# BareBonesArduino-OtherMill-BottomOnly.net
KiCad netlist of a schematic drawn in EAGLE
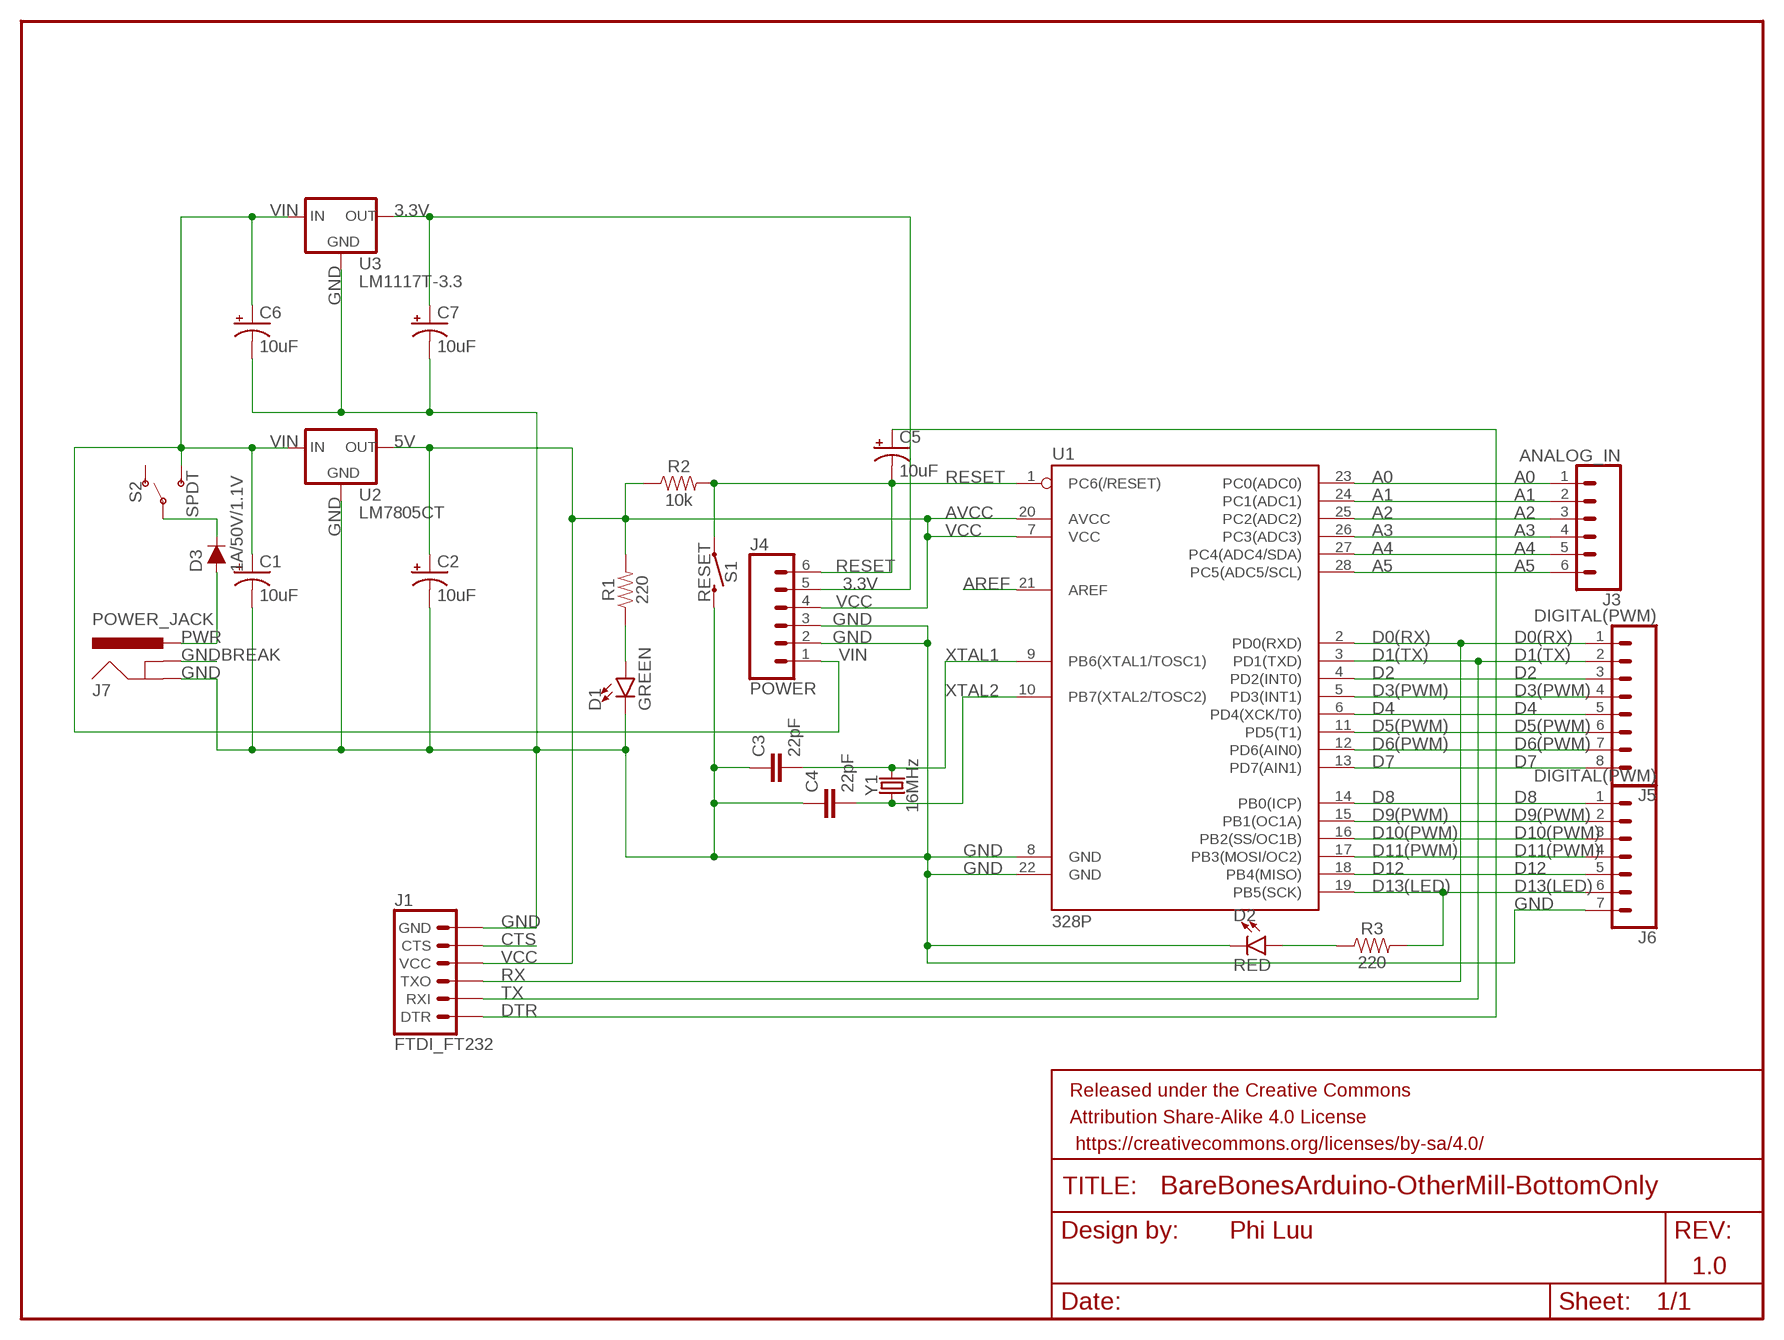
[diagram p0: schematic, sheet 1]

(export (version "E")
  (design (tool "Eeschema 10.0.6"))
  (components
    (comp (ref "C1")
      (value "10uF")
      (footprint "eagle-import:CPOL-RADIAL-2.5MM-5MM")
      (libsource (lib "eagle-import") (part "10UF-POLAR-RADIAL-2.5MM-25V-20%"))
    )
    (comp (ref "C2")
      (value "10uF")
      (footprint "eagle-import:CPOL-RADIAL-2.5MM-5MM")
      (libsource (lib "eagle-import") (part "10UF-POLAR-RADIAL-2.5MM-25V-20%"))
    )
    (comp (ref "C3")
      (value "22pF")
      (footprint "eagle-import:CAP-PTH-2.54")
      (libsource (lib "eagle-import") (part "22PF-PTH-2.54MM-200V-5%"))
    )
    (comp (ref "C4")
      (value "22pF")
      (footprint "eagle-import:CAP-PTH-2.54")
      (libsource (lib "eagle-import") (part "22PF-PTH-2.54MM-200V-5%"))
    )
    (comp (ref "C5")
      (value "10uF")
      (footprint "eagle-import:CPOL-RADIAL-2.5MM-5MM")
      (libsource (lib "eagle-import") (part "10UF-POLAR-RADIAL-2.5MM-25V-20%"))
    )
    (comp (ref "C6")
      (value "10uF")
      (footprint "eagle-import:CPOL-RADIAL-2.5MM-5MM")
      (libsource (lib "eagle-import") (part "10UF-POLAR-RADIAL-2.5MM-25V-20%"))
    )
    (comp (ref "C7")
      (value "10uF")
      (footprint "eagle-import:CPOL-RADIAL-2.5MM-5MM")
      (libsource (lib "eagle-import") (part "10UF-POLAR-RADIAL-2.5MM-25V-20%"))
    )
    (comp (ref "D1")
      (value "GREEN")
      (footprint "eagle-import:LED_5MM")
      (libsource (lib "eagle-import") (part "LED5MM"))
    )
    (comp (ref "D2")
      (value "RED")
      (footprint "eagle-import:LED_5MM")
      (libsource (lib "eagle-import") (part "LED5MM"))
    )
    (comp (ref "D3")
      (value "1A/50V/1.1V")
      (footprint "eagle-import:DIODE-1N4001")
      (libsource (lib "eagle-import") (part "DIODE-PTH"))
    )
    (comp (ref "FRAME1")
      (value "FRAME-LETTER")
      (footprint "eagle-import:CREATIVE_COMMONS")
      (libsource (lib "eagle-import") (part "FRAME-LETTER"))
    )
    (comp (ref "J1")
      (value "FTDI_FT232")
      (footprint "eagle-import:1X06")
      (libsource (lib "eagle-import") (part "6_PIN_SERIAL_TARGET"))
    )
    (comp (ref "J3")
      (value "ANALOG_IN")
      (footprint "eagle-import:1X06")
      (libsource (lib "eagle-import") (part "CONN_06SILK_FEMALE_PTH"))
    )
    (comp (ref "J4")
      (value "POWER")
      (footprint "eagle-import:1X06")
      (libsource (lib "eagle-import") (part "CONN_06SILK_FEMALE_PTH"))
    )
    (comp (ref "J5")
      (value "DIGITAL(PWM)")
      (footprint "eagle-import:1X08")
      (libsource (lib "eagle-import") (part "CONN_08{dblquote}"))
    )
    (comp (ref "J6")
      (value "DIGITAL(PWM)")
      (footprint "eagle-import:1X07")
      (libsource (lib "eagle-import") (part "CONN_07"))
    )
    (comp (ref "J7")
      (value "POWER_JACK")
      (footprint "eagle-import:POWER_JACK_PTH")
      (libsource (lib "eagle-import") (part "POWER_JACK"))
    )
    (comp (ref "R1")
      (value "220")
      (footprint "eagle-import:AXIAL-0.3")
      (libsource (lib "eagle-import") (part "1KOHM-HORIZ-1/4W-5%"))
    )
    (comp (ref "R2")
      (value "10k")
      (footprint "eagle-import:AXIAL-0.3")
      (libsource (lib "eagle-import") (part "10KOHM-HORIZ-1/4W-5%"))
    )
    (comp (ref "R3")
      (value "220")
      (footprint "eagle-import:AXIAL-0.3")
      (libsource (lib "eagle-import") (part "1KOHM-HORIZ-1/4W-5%"))
    )
    (comp (ref "S1")
      (value "RESET")
      (footprint "eagle-import:TACTILE_SWITCH_PTH_6.0MM")
      (libsource (lib "eagle-import") (part "MOMENTARY-SWITCH-SPST-PTH-6.0MM"))
    )
    (comp (ref "S2")
      (value "SPDT")
      (footprint "eagle-import:SWITCH_SPDT_PTH_11.6X4.0MM")
      (libsource (lib "eagle-import") (part "SWITCH-SPDT-PTH-11.6X4.0MM"))
    )
    (comp (ref "U1")
      (value "328P")
      (footprint "eagle-import:DIP28")
      (libsource (lib "eagle-import") (part "ATMEGA328P_PDIP"))
    )
    (comp (ref "U2")
      (value "LM7805CT")
      (footprint "eagle-import:TO-220-ALT")
      (libsource (lib "eagle-import") (part "V_REG_78XX-TO-220"))
    )
    (comp (ref "U3")
      (value "LM1117T-3.3")
      (footprint "eagle-import:78XXL")
      (libsource (lib "eagle-import") (part "V_REG_LD1117VXX"))
    )
    (comp (ref "Y1")
      (value "16MHz")
      (footprint "eagle-import:HC49US")
      (libsource (lib "eagle-import") (part "CRYSTAL-16MHZPTH-HC49US"))
    )
  )
  (nets
    (net (code "1") (name "/3.3V") (class "Default")
      (node (ref "C7") (pin "1") (pinfunction "+_1") (pintype "passive"))
      (node (ref "J4") (pin "5") (pinfunction "5_5") (pintype "passive"))
      (node (ref "U3") (pin "GND") (pinfunction "OUT_GND") (pintype "passive"))
    )
    (net (code "2") (name "/A0") (class "Default")
      (node (ref "J3") (pin "1") (pinfunction "1_1") (pintype "passive"))
      (node (ref "U1") (pin "23") (pinfunction "PC0(ADC0)_23") (pintype "bidirectional"))
    )
    (net (code "3") (name "/A1") (class "Default")
      (node (ref "J3") (pin "2") (pinfunction "2_2") (pintype "passive"))
      (node (ref "U1") (pin "24") (pinfunction "PC1(ADC1)_24") (pintype "bidirectional"))
    )
    (net (code "4") (name "/A2") (class "Default")
      (node (ref "J3") (pin "3") (pinfunction "3_3") (pintype "passive"))
      (node (ref "U1") (pin "25") (pinfunction "PC2(ADC2)_25") (pintype "bidirectional"))
    )
    (net (code "5") (name "/A3") (class "Default")
      (node (ref "J3") (pin "4") (pinfunction "4_4") (pintype "passive"))
      (node (ref "U1") (pin "26") (pinfunction "PC3(ADC3)_26") (pintype "bidirectional"))
    )
    (net (code "6") (name "/A4") (class "Default")
      (node (ref "J3") (pin "5") (pinfunction "5_5") (pintype "passive"))
      (node (ref "U1") (pin "27") (pinfunction "PC4(ADC4/SDA)_27") (pintype "bidirectional"))
    )
    (net (code "7") (name "/A5") (class "Default")
      (node (ref "J3") (pin "6") (pinfunction "6_6") (pintype "passive"))
      (node (ref "U1") (pin "28") (pinfunction "PC5(ADC5/SCL)_28") (pintype "bidirectional"))
    )
    (net (code "8") (name "/AREF") (class "Default")
      (node (ref "U1") (pin "21") (pinfunction "AREF_21") (pintype "bidirectional"))
    )
    (net (code "9") (name "/CTS") (class "Default")
      (node (ref "J1") (pin "5") (pinfunction "CTS_5") (pintype "passive"))
    )
    (net (code "10") (name "/D0(RX)") (class "Default")
      (node (ref "J1") (pin "3") (pinfunction "TXO_3") (pintype "passive"))
      (node (ref "J5") (pin "1") (pinfunction "1_1") (pintype "passive"))
      (node (ref "U1") (pin "2") (pinfunction "PD0(RXD)_2") (pintype "bidirectional"))
    )
    (net (code "11") (name "/D1(TX)") (class "Default")
      (node (ref "J1") (pin "2") (pinfunction "RXI_2") (pintype "passive"))
      (node (ref "J5") (pin "2") (pinfunction "2_2") (pintype "passive"))
      (node (ref "U1") (pin "3") (pinfunction "PD1(TXD)_3") (pintype "bidirectional"))
    )
    (net (code "12") (name "/D2") (class "Default")
      (node (ref "J5") (pin "3") (pinfunction "3_3") (pintype "passive"))
      (node (ref "U1") (pin "4") (pinfunction "PD2(INT0)_4") (pintype "bidirectional"))
    )
    (net (code "13") (name "/D3(PWM)") (class "Default")
      (node (ref "J5") (pin "4") (pinfunction "4_4") (pintype "passive"))
      (node (ref "U1") (pin "5") (pinfunction "PD3(INT1)_5") (pintype "bidirectional"))
    )
    (net (code "14") (name "/D4") (class "Default")
      (node (ref "J5") (pin "5") (pinfunction "5_5") (pintype "passive"))
      (node (ref "U1") (pin "6") (pinfunction "PD4(XCK/T0)_6") (pintype "bidirectional"))
    )
    (net (code "15") (name "/D5(PWM)") (class "Default")
      (node (ref "J5") (pin "6") (pinfunction "6_6") (pintype "passive"))
      (node (ref "U1") (pin "11") (pinfunction "PD5(T1)_11") (pintype "bidirectional"))
    )
    (net (code "16") (name "/D6(PWM)") (class "Default")
      (node (ref "J5") (pin "7") (pinfunction "7_7") (pintype "passive"))
      (node (ref "U1") (pin "12") (pinfunction "PD6(AIN0)_12") (pintype "bidirectional"))
    )
    (net (code "17") (name "/D7") (class "Default")
      (node (ref "J5") (pin "8") (pinfunction "8_8") (pintype "passive"))
      (node (ref "U1") (pin "13") (pinfunction "PD7(AIN1)_13") (pintype "bidirectional"))
    )
    (net (code "18") (name "/D8") (class "Default")
      (node (ref "J6") (pin "1") (pinfunction "1_1") (pintype "passive"))
      (node (ref "U1") (pin "14") (pinfunction "PB0(ICP)_14") (pintype "bidirectional"))
    )
    (net (code "19") (name "/D9(PWM)") (class "Default")
      (node (ref "J6") (pin "2") (pinfunction "2_2") (pintype "passive"))
      (node (ref "U1") (pin "15") (pinfunction "PB1(OC1A)_15") (pintype "bidirectional"))
    )
    (net (code "20") (name "/D10(PWM)") (class "Default")
      (node (ref "J6") (pin "3") (pinfunction "3_3") (pintype "passive"))
      (node (ref "U1") (pin "16") (pinfunction "PB2(SS/OC1B)_16") (pintype "bidirectional"))
    )
    (net (code "21") (name "/D11(PWM)") (class "Default")
      (node (ref "J6") (pin "4") (pinfunction "4_4") (pintype "passive"))
      (node (ref "U1") (pin "17") (pinfunction "PB3(MOSI/OC2)_17") (pintype "bidirectional"))
    )
    (net (code "22") (name "/D12") (class "Default")
      (node (ref "J6") (pin "5") (pinfunction "5_5") (pintype "passive"))
      (node (ref "U1") (pin "18") (pinfunction "PB4(MISO)_18") (pintype "bidirectional"))
    )
    (net (code "23") (name "/D13(LED)") (class "Default")
      (node (ref "J6") (pin "6") (pinfunction "6_6") (pintype "passive"))
      (node (ref "R3") (pin "P$2") (pinfunction "2_P$2") (pintype "passive"))
      (node (ref "U1") (pin "19") (pinfunction "PB5(SCK)_19") (pintype "bidirectional"))
    )
    (net (code "24") (name "/DTR") (class "Default")
      (node (ref "C5") (pin "1") (pinfunction "+_1") (pintype "passive"))
      (node (ref "J1") (pin "1") (pinfunction "DTR_1") (pintype "passive"))
    )
    (net (code "25") (name "/GND") (class "Default")
      (node (ref "C1") (pin "2") (pinfunction "-_2") (pintype "passive"))
      (node (ref "C2") (pin "2") (pinfunction "-_2") (pintype "passive"))
      (node (ref "C3") (pin "1") (pinfunction "1_1") (pintype "passive"))
      (node (ref "C4") (pin "1") (pinfunction "1_1") (pintype "passive"))
      (node (ref "C6") (pin "2") (pinfunction "-_2") (pintype "passive"))
      (node (ref "C7") (pin "2") (pinfunction "-_2") (pintype "passive"))
      (node (ref "D1") (pin "K") (pinfunction "C_K") (pintype "passive"))
      (node (ref "D2") (pin "K") (pinfunction "C_K") (pintype "passive"))
      (node (ref "J1") (pin "6") (pinfunction "GND_6") (pintype "passive"))
      (node (ref "J4") (pin "2") (pinfunction "2_2") (pintype "passive"))
      (node (ref "J4") (pin "3") (pinfunction "3_3") (pintype "passive"))
      (node (ref "J6") (pin "7") (pinfunction "7_7") (pintype "passive"))
      (node (ref "J7") (pin "GND") (pinfunction "GND_GND") (pintype "bidirectional"))
      (node (ref "S1") (pin "3") (pinfunction "2_3") (pintype "passive"))
      (node (ref "U1") (pin "22") (pinfunction "GND_22") (pintype "bidirectional"))
      (node (ref "U1") (pin "8") (pinfunction "GND_8") (pintype "bidirectional"))
      (node (ref "U2") (pin "GND") (pinfunction "GND_GND") (pintype "input"))
      (node (ref "U3") (pin "IN") (pinfunction "GND_IN") (pintype "input"))
    )
    (net (code "26") (name "/GNDBREAK") (class "Default")
      (node (ref "J7") (pin "GNDBREAK") (pinfunction "GNDBREAK_GNDBREAK") (pintype "bidirectional"))
    )
    (net (code "27") (name "/PWR") (class "Default")
      (node (ref "D3") (pin "A") (pinfunction "A_A") (pintype "passive"))
      (node (ref "J7") (pin "PWR") (pinfunction "PWR_PWR") (pintype "bidirectional"))
    )
    (net (code "28") (name "/RESET") (class "Default")
      (node (ref "C5") (pin "2") (pinfunction "-_2") (pintype "passive"))
      (node (ref "J4") (pin "6") (pinfunction "6_6") (pintype "passive"))
      (node (ref "R2") (pin "P$2") (pinfunction "2_P$2") (pintype "passive"))
      (node (ref "S1") (pin "1") (pinfunction "1_1") (pintype "passive"))
      (node (ref "U1") (pin "1") (pinfunction "PC6(/RESET)_1") (pintype "bidirectional"))
    )
    (net (code "29") (name "/VCC") (class "Default")
      (node (ref "C2") (pin "1") (pinfunction "+_1") (pintype "passive"))
      (node (ref "J1") (pin "4") (pinfunction "VCC_4") (pintype "passive"))
      (node (ref "J4") (pin "4") (pinfunction "4_4") (pintype "passive"))
      (node (ref "R1") (pin "P$2") (pinfunction "2_P$2") (pintype "passive"))
      (node (ref "R2") (pin "P$1") (pinfunction "1_P$1") (pintype "passive"))
      (node (ref "U1") (pin "20") (pinfunction "AVCC_20") (pintype "bidirectional"))
      (node (ref "U1") (pin "7") (pinfunction "VCC_7") (pintype "bidirectional"))
      (node (ref "U2") (pin "OUT") (pinfunction "OUT_OUT") (pintype "passive"))
    )
    (net (code "30") (name "/VIN") (class "Default")
      (node (ref "C1") (pin "1") (pinfunction "+_1") (pintype "passive"))
      (node (ref "C6") (pin "1") (pinfunction "+_1") (pintype "passive"))
      (node (ref "J4") (pin "1") (pinfunction "1_1") (pintype "passive"))
      (node (ref "S2") (pin "3") (pinfunction "S_3") (pintype "passive"))
      (node (ref "U2") (pin "IN") (pinfunction "IN_IN") (pintype "input"))
      (node (ref "U3") (pin "OUT") (pinfunction "IN_OUT") (pintype "input"))
    )
    (net (code "31") (name "/XTAL1") (class "Default")
      (node (ref "C3") (pin "2") (pinfunction "2_2") (pintype "passive"))
      (node (ref "U1") (pin "9") (pinfunction "PB6(XTAL1/TOSC1)_9") (pintype "bidirectional"))
      (node (ref "Y1") (pin "2") (pinfunction "2_2") (pintype "passive"))
    )
    (net (code "32") (name "/XTAL2") (class "Default")
      (node (ref "C4") (pin "2") (pinfunction "2_2") (pintype "passive"))
      (node (ref "U1") (pin "10") (pinfunction "PB7(XTAL2/TOSC2)_10") (pintype "bidirectional"))
      (node (ref "Y1") (pin "1") (pinfunction "1_1") (pintype "passive"))
    )
    (net (code "33") (name "Net-(R1-1)") (class "Default")
      (node (ref "D1") (pin "A") (pinfunction "A_A") (pintype "passive"))
      (node (ref "R1") (pin "P$1") (pinfunction "1_P$1") (pintype "passive"))
    )
    (net (code "34") (name "Net-(R3-1)") (class "Default")
      (node (ref "D2") (pin "A") (pinfunction "A_A") (pintype "passive"))
      (node (ref "R3") (pin "P$1") (pinfunction "1_P$1") (pintype "passive"))
    )
    (net (code "35") (name "Net-(S2-P)") (class "Default")
      (node (ref "D3") (pin "C") (pinfunction "C_C") (pintype "passive"))
      (node (ref "S2") (pin "2") (pinfunction "P_2") (pintype "passive"))
    )
    (net (code "36") (name "unconnected-(S2-O-Pad1)") (class "Default")
      (node (ref "S2") (pin "1") (pinfunction "O_1") (pintype "passive"))
    )
  )
)
